# AktuatorPlatine.net
KiCad netlist of a schematic drawn in EAGLE
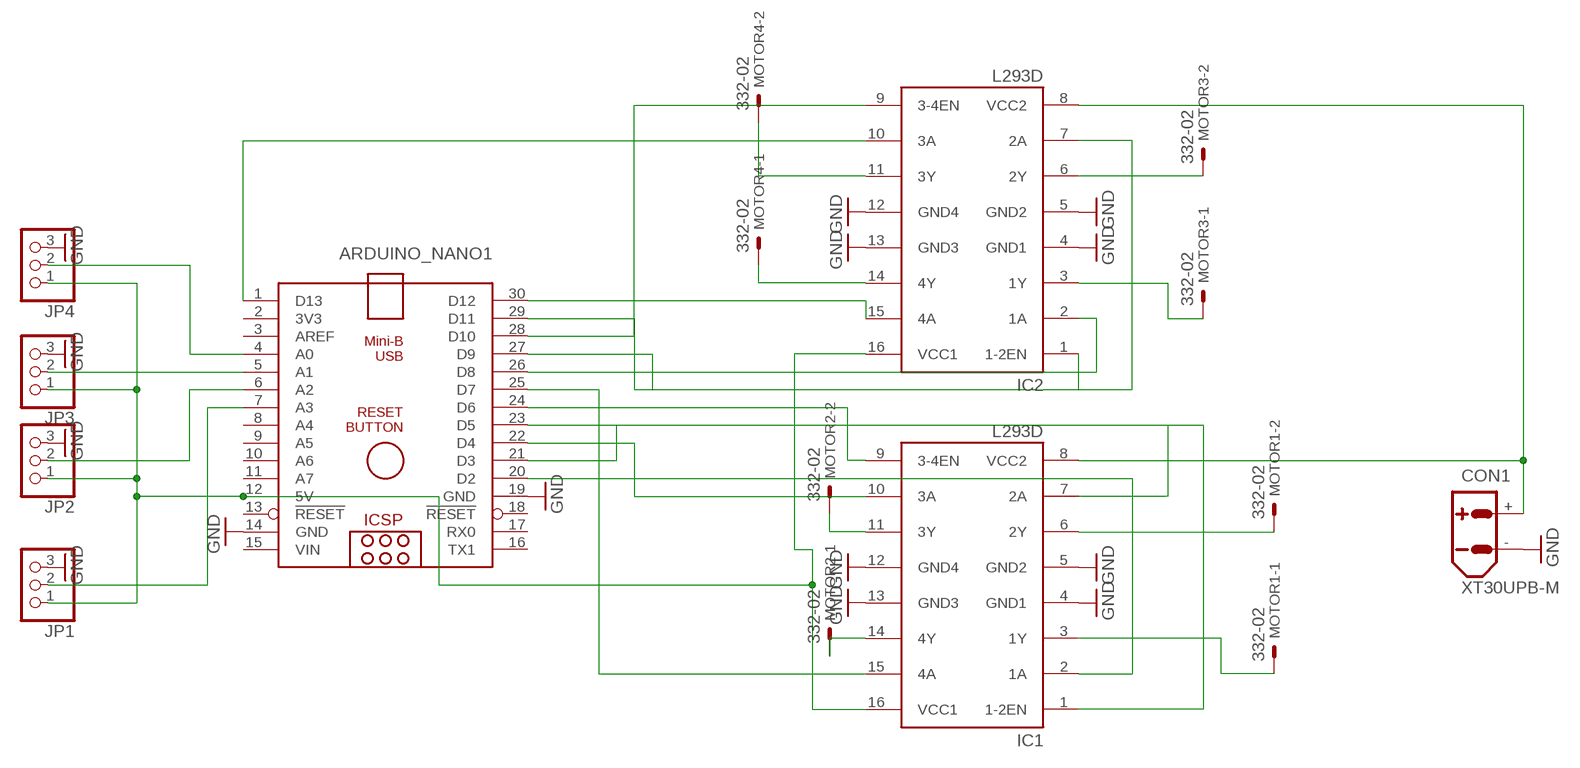
[diagram p0: schematic, sheet 1]

(export (version "E")
  (design (tool "Eeschema 10.0.6"))
  (components
    (comp (ref "ARDUINO_NANO1")
      (value "ARDUINO_NANO")
      (footprint "eagle-import:ARDUINO_NANO")
      (libsource (lib "eagle-import") (part "ARDUINO_NANO"))
    )
    (comp (ref "CON1")
      (value "XT30UPB-M")
      (footprint "eagle-import:XT30UPB-M")
      (libsource (lib "eagle-import") (part "XT30UPB-M"))
    )
    (comp (ref "IC1")
      (value "L293D")
      (footprint "eagle-import:DIL16")
      (libsource (lib "eagle-import") (part "L293D"))
    )
    (comp (ref "IC2")
      (value "L293D")
      (footprint "eagle-import:DIL16")
      (libsource (lib "eagle-import") (part "L293D"))
    )
    (comp (ref "JP1")
      (value "PINHD-1X3")
      (footprint "eagle-import:1X03")
      (libsource (lib "eagle-import") (part "PINHD-1X3"))
    )
    (comp (ref "JP2")
      (value "PINHD-1X3")
      (footprint "eagle-import:1X03")
      (libsource (lib "eagle-import") (part "PINHD-1X3"))
    )
    (comp (ref "JP3")
      (value "PINHD-1X3")
      (footprint "eagle-import:1X03")
      (libsource (lib "eagle-import") (part "PINHD-1X3"))
    )
    (comp (ref "JP4")
      (value "PINHD-1X3")
      (footprint "eagle-import:1X03")
      (libsource (lib "eagle-import") (part "PINHD-1X3"))
    )
    (comp (ref "MOTOR1")
      (value "332-02")
      (footprint "eagle-import:332-02")
      (libsource (lib "eagle-import") (part "332-02"))
    )
    (comp (ref "MOTOR2")
      (value "332-02")
      (footprint "eagle-import:332-02")
      (libsource (lib "eagle-import") (part "332-02"))
    )
    (comp (ref "MOTOR3")
      (value "332-02")
      (footprint "eagle-import:332-02")
      (libsource (lib "eagle-import") (part "332-02"))
    )
    (comp (ref "MOTOR4")
      (value "332-02")
      (footprint "eagle-import:332-02")
      (libsource (lib "eagle-import") (part "332-02"))
    )
  )
  (nets
    (net (code "1") (name "/VIN") (class "Default")
      (node (ref "ARDUINO_NANO1") (pin "15") (pinfunction "VIN_15") (pintype "power_in"))
    )
    (net (code "2") (name "GND") (class "Default")
      (node (ref "ARDUINO_NANO1") (pin "14") (pinfunction "GND_14") (pintype "power_in"))
      (node (ref "ARDUINO_NANO1") (pin "19") (pinfunction "GND_19") (pintype "power_in"))
      (node (ref "CON1") (pin "-") (pinfunction "-_-") (pintype "power_in"))
      (node (ref "IC1") (pin "12") (pinfunction "GND4_12") (pintype "power_in"))
      (node (ref "IC1") (pin "13") (pinfunction "GND3_13") (pintype "power_in"))
      (node (ref "IC1") (pin "4") (pinfunction "GND1_4") (pintype "power_in"))
      (node (ref "IC1") (pin "5") (pinfunction "GND2_5") (pintype "power_in"))
      (node (ref "IC2") (pin "12") (pinfunction "GND4_12") (pintype "power_in"))
      (node (ref "IC2") (pin "13") (pinfunction "GND3_13") (pintype "power_in"))
      (node (ref "IC2") (pin "4") (pinfunction "GND1_4") (pintype "power_in"))
      (node (ref "IC2") (pin "5") (pinfunction "GND2_5") (pintype "power_in"))
      (node (ref "JP1") (pin "3") (pinfunction "3_3") (pintype "passive"))
      (node (ref "JP2") (pin "3") (pinfunction "3_3") (pintype "passive"))
      (node (ref "JP3") (pin "3") (pinfunction "3_3") (pintype "passive"))
      (node (ref "JP4") (pin "3") (pinfunction "3_3") (pintype "passive"))
    )
    (net (code "3") (name "Net-(ARDUINO_NANO1-5V)") (class "Default")
      (node (ref "ARDUINO_NANO1") (pin "12") (pinfunction "5V_12") (pintype "power_in"))
      (node (ref "IC1") (pin "16") (pinfunction "VCC1_16") (pintype "power_in"))
      (node (ref "IC2") (pin "16") (pinfunction "VCC1_16") (pintype "power_in"))
      (node (ref "JP1") (pin "1") (pinfunction "1_1") (pintype "passive"))
      (node (ref "JP2") (pin "1") (pinfunction "1_1") (pintype "passive"))
      (node (ref "JP3") (pin "1") (pinfunction "1_1") (pintype "passive"))
      (node (ref "JP4") (pin "1") (pinfunction "1_1") (pintype "passive"))
    )
    (net (code "4") (name "Net-(ARDUINO_NANO1-A0)") (class "Default")
      (node (ref "ARDUINO_NANO1") (pin "4") (pinfunction "A0_4") (pintype "bidirectional"))
      (node (ref "JP4") (pin "2") (pinfunction "2_2") (pintype "passive"))
    )
    (net (code "5") (name "Net-(ARDUINO_NANO1-A1)") (class "Default")
      (node (ref "ARDUINO_NANO1") (pin "5") (pinfunction "A1_5") (pintype "bidirectional"))
      (node (ref "JP3") (pin "2") (pinfunction "2_2") (pintype "passive"))
    )
    (net (code "6") (name "Net-(ARDUINO_NANO1-A2)") (class "Default")
      (node (ref "ARDUINO_NANO1") (pin "6") (pinfunction "A2_6") (pintype "bidirectional"))
      (node (ref "JP2") (pin "2") (pinfunction "2_2") (pintype "passive"))
    )
    (net (code "7") (name "Net-(ARDUINO_NANO1-A3)") (class "Default")
      (node (ref "ARDUINO_NANO1") (pin "7") (pinfunction "A3_7") (pintype "bidirectional"))
      (node (ref "JP1") (pin "2") (pinfunction "2_2") (pintype "passive"))
    )
    (net (code "8") (name "Net-(ARDUINO_NANO1-D2)") (class "Default")
      (node (ref "ARDUINO_NANO1") (pin "20") (pinfunction "D2_20") (pintype "bidirectional"))
      (node (ref "IC1") (pin "2") (pinfunction "1A_2") (pintype "input"))
    )
    (net (code "9") (name "Net-(ARDUINO_NANO1-D3)") (class "Default")
      (node (ref "ARDUINO_NANO1") (pin "21") (pinfunction "D3_21") (pintype "bidirectional"))
      (node (ref "IC1") (pin "7") (pinfunction "2A_7") (pintype "input"))
    )
    (net (code "10") (name "Net-(ARDUINO_NANO1-D4)") (class "Default")
      (node (ref "ARDUINO_NANO1") (pin "22") (pinfunction "D4_22") (pintype "bidirectional"))
      (node (ref "IC1") (pin "10") (pinfunction "3A_10") (pintype "input"))
    )
    (net (code "11") (name "Net-(ARDUINO_NANO1-D5)") (class "Default")
      (node (ref "ARDUINO_NANO1") (pin "23") (pinfunction "D5_23") (pintype "bidirectional"))
      (node (ref "IC1") (pin "1") (pinfunction "1-2EN_1") (pintype "input"))
    )
    (net (code "12") (name "Net-(ARDUINO_NANO1-D6)") (class "Default")
      (node (ref "ARDUINO_NANO1") (pin "24") (pinfunction "D6_24") (pintype "bidirectional"))
      (node (ref "IC1") (pin "9") (pinfunction "3-4EN_9") (pintype "input"))
    )
    (net (code "13") (name "Net-(ARDUINO_NANO1-D7)") (class "Default")
      (node (ref "ARDUINO_NANO1") (pin "25") (pinfunction "D7_25") (pintype "bidirectional"))
      (node (ref "IC1") (pin "15") (pinfunction "4A_15") (pintype "input"))
    )
    (net (code "14") (name "Net-(ARDUINO_NANO1-D8)") (class "Default")
      (node (ref "ARDUINO_NANO1") (pin "26") (pinfunction "D8_26") (pintype "bidirectional"))
      (node (ref "IC2") (pin "2") (pinfunction "1A_2") (pintype "input"))
    )
    (net (code "15") (name "Net-(ARDUINO_NANO1-D9)") (class "Default")
      (node (ref "ARDUINO_NANO1") (pin "27") (pinfunction "D9_27") (pintype "bidirectional"))
      (node (ref "IC2") (pin "1") (pinfunction "1-2EN_1") (pintype "input"))
    )
    (net (code "16") (name "Net-(ARDUINO_NANO1-D10)") (class "Default")
      (node (ref "ARDUINO_NANO1") (pin "28") (pinfunction "D10_28") (pintype "bidirectional"))
      (node (ref "IC2") (pin "9") (pinfunction "3-4EN_9") (pintype "input"))
    )
    (net (code "17") (name "Net-(ARDUINO_NANO1-D11)") (class "Default")
      (node (ref "ARDUINO_NANO1") (pin "29") (pinfunction "D11_29") (pintype "bidirectional"))
      (node (ref "IC2") (pin "7") (pinfunction "2A_7") (pintype "input"))
    )
    (net (code "18") (name "Net-(ARDUINO_NANO1-D12)") (class "Default")
      (node (ref "ARDUINO_NANO1") (pin "30") (pinfunction "D12_30") (pintype "bidirectional"))
      (node (ref "IC2") (pin "15") (pinfunction "4A_15") (pintype "input"))
    )
    (net (code "19") (name "Net-(ARDUINO_NANO1-D13)") (class "Default")
      (node (ref "ARDUINO_NANO1") (pin "1") (pinfunction "D13_1") (pintype "bidirectional"))
      (node (ref "IC2") (pin "10") (pinfunction "3A_10") (pintype "input"))
    )
    (net (code "20") (name "Net-(IC1-1Y)") (class "Default")
      (node (ref "IC1") (pin "3") (pinfunction "1Y_3") (pintype "output"))
      (node (ref "MOTOR1") (pin "1") (pinfunction "S_1") (pintype "passive"))
    )
    (net (code "21") (name "Net-(IC1-2Y)") (class "Default")
      (node (ref "IC1") (pin "6") (pinfunction "2Y_6") (pintype "output"))
      (node (ref "MOTOR1") (pin "2") (pinfunction "S_2") (pintype "passive"))
    )
    (net (code "22") (name "Net-(IC1-3Y)") (class "Default")
      (node (ref "IC1") (pin "11") (pinfunction "3Y_11") (pintype "output"))
      (node (ref "MOTOR2") (pin "2") (pinfunction "S_2") (pintype "passive"))
    )
    (net (code "23") (name "Net-(IC1-4Y)") (class "Default")
      (node (ref "IC1") (pin "14") (pinfunction "4Y_14") (pintype "output"))
      (node (ref "MOTOR2") (pin "1") (pinfunction "S_1") (pintype "passive"))
    )
    (net (code "24") (name "Net-(IC1-VCC2)") (class "Default")
      (node (ref "CON1") (pin "+") (pinfunction "+_+") (pintype "power_in"))
      (node (ref "IC1") (pin "8") (pinfunction "VCC2_8") (pintype "power_in"))
      (node (ref "IC2") (pin "8") (pinfunction "VCC2_8") (pintype "power_in"))
    )
    (net (code "25") (name "Net-(IC2-1Y)") (class "Default")
      (node (ref "IC2") (pin "3") (pinfunction "1Y_3") (pintype "output"))
      (node (ref "MOTOR3") (pin "1") (pinfunction "S_1") (pintype "passive"))
    )
    (net (code "26") (name "Net-(IC2-2Y)") (class "Default")
      (node (ref "IC2") (pin "6") (pinfunction "2Y_6") (pintype "output"))
      (node (ref "MOTOR3") (pin "2") (pinfunction "S_2") (pintype "passive"))
    )
    (net (code "27") (name "Net-(IC2-3Y)") (class "Default")
      (node (ref "IC2") (pin "11") (pinfunction "3Y_11") (pintype "output"))
      (node (ref "MOTOR4") (pin "2") (pinfunction "S_2") (pintype "passive"))
    )
    (net (code "28") (name "Net-(IC2-4Y)") (class "Default")
      (node (ref "IC2") (pin "14") (pinfunction "4Y_14") (pintype "output"))
      (node (ref "MOTOR4") (pin "1") (pinfunction "S_1") (pintype "passive"))
    )
    (net (code "29") (name "unconnected-(ARDUINO_NANO1-3V3-Pad2)") (class "Default")
      (node (ref "ARDUINO_NANO1") (pin "2") (pinfunction "3V3_2") (pintype "output"))
    )
    (net (code "30") (name "unconnected-(ARDUINO_NANO1-A4-Pad8)") (class "Default")
      (node (ref "ARDUINO_NANO1") (pin "8") (pinfunction "A4_8") (pintype "bidirectional"))
    )
    (net (code "31") (name "unconnected-(ARDUINO_NANO1-A5-Pad9)") (class "Default")
      (node (ref "ARDUINO_NANO1") (pin "9") (pinfunction "A5_9") (pintype "bidirectional"))
    )
    (net (code "32") (name "unconnected-(ARDUINO_NANO1-A6-Pad10)") (class "Default")
      (node (ref "ARDUINO_NANO1") (pin "10") (pinfunction "A6_10") (pintype "bidirectional"))
    )
    (net (code "33") (name "unconnected-(ARDUINO_NANO1-A7-Pad11)") (class "Default")
      (node (ref "ARDUINO_NANO1") (pin "11") (pinfunction "A7_11") (pintype "bidirectional"))
    )
    (net (code "34") (name "unconnected-(ARDUINO_NANO1-AREF-Pad3)") (class "Default")
      (node (ref "ARDUINO_NANO1") (pin "3") (pinfunction "AREF_3") (pintype "input"))
    )
    (net (code "35") (name "unconnected-(ARDUINO_NANO1-RX0-Pad17)") (class "Default")
      (node (ref "ARDUINO_NANO1") (pin "17") (pinfunction "RX0_17") (pintype "bidirectional"))
    )
    (net (code "36") (name "unconnected-(ARDUINO_NANO1-TX1-Pad16)") (class "Default")
      (node (ref "ARDUINO_NANO1") (pin "16") (pinfunction "TX1_16") (pintype "bidirectional"))
    )
    (net (code "37") (name "unconnected-(ARDUINO_NANO1-~{RESET}-Pad13)") (class "Default")
      (node (ref "ARDUINO_NANO1") (pin "13") (pinfunction "~{RESET}_13") (pintype "input"))
    )
    (net (code "38") (name "unconnected-(ARDUINO_NANO1-~{RESET}-Pad18)") (class "Default")
      (node (ref "ARDUINO_NANO1") (pin "18") (pinfunction "~{RESET}_18") (pintype "input"))
    )
  )
)
